# Deel_2_transistor.net
KiCad netlist of a schematic drawn in Altium Designer
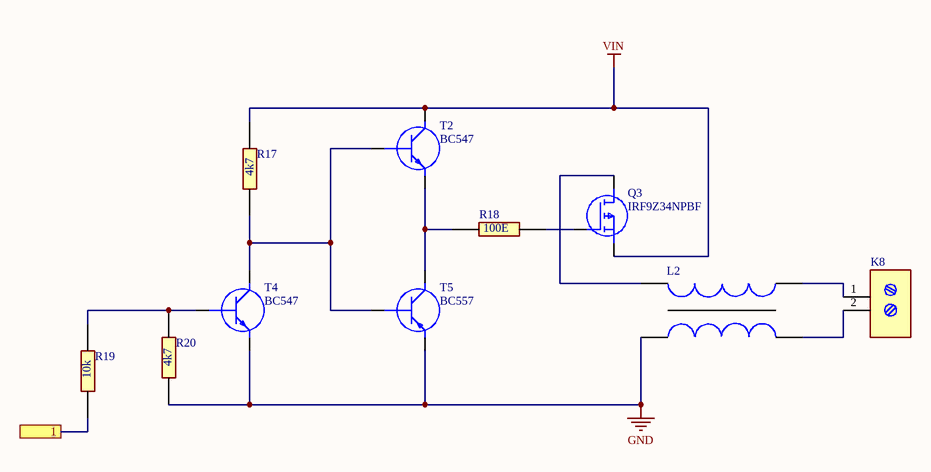
[diagram p0: Deel_2_transistor.SchDoc]

(export (version "E")
  (design (tool "Eeschema 10.0.6"))
  (components
    (comp (ref "K8")
      (value "schroefconnector")
      (footprint "PcbLib1:schroefconnector")
      (description "Connector 1716020000")
      (fields (field (name "MANUFACTURER_PART_NUMBER") "1716020000"))
      (libsource (lib "Schlib_soldeerstation") (part "schroefconnector"))
    )
    (comp (ref "L2")
      (value "cmsmoorspoel")
      (footprint "PcbLib1:CMsmoorspoel")
      (description "Transformer CM2545X171B-10")
      (fields (field (name "MANUFACTURER_PART_NUMBER") "CM2545X171B-10"))
      (libsource (lib "Schlib_soldeerstation") (part "cmsmoorspoel"))
    )
    (comp (ref "Q3")
      (value "IRF9Z34NPBF")
      (footprint "PcbLib1:irf9z34npbf")
      (description "MOSFET (P-Channel)")
      (fields (field (name "MOUSER2 PART NUMBER") "942-IRF9Z34NPBF"))
      (libsource (lib "Schlib_soldeerstation") (part "IRF9Z34NPBF"))
    )
    (comp (ref "R17")
      (value "4k7")
      (footprint "PcbLib1:4k7")
      (description "Resistor")
      (fields
        (field (name "MANUFACTURER_PART_NUMBER") "CPF0805B100RE1")
        (field (name "MOUSER PART NUMBER") "279-CPF0805B100RE1")
      )
      (libsource (lib "Schlib_soldeerstation") (part "4k7"))
    )
    (comp (ref "R18")
      (value "100E")
      (footprint "PcbLib1:100ohm")
      (description "Resistor")
      (fields
        (field (name "MANUFACTURER_PART_NUMBER") "CPF0805B100RE1")
        (field (name "MOUSER PART NUMBER") "279-CPF0805B100RE1")
      )
      (libsource (lib "Schlib_soldeerstation") (part "100ohm"))
    )
    (comp (ref "R19")
      (value "10k")
      (footprint "PcbLib1:10k")
      (description "Resistor")
      (fields
        (field (name "MANUFACTURER_PART_NUMBER") "CPF0805B100RE1")
        (field (name "MOUSER PART NUMBER") "279-CPF0805B100RE1")
      )
      (libsource (lib "Schlib_soldeerstation") (part "10k"))
    )
    (comp (ref "R20")
      (value "4k7")
      (footprint "PcbLib1:4k7")
      (description "Resistor")
      (fields
        (field (name "MANUFACTURER_PART_NUMBER") "CPF0805B100RE1")
        (field (name "MOUSER PART NUMBER") "279-CPF0805B100RE1")
      )
      (libsource (lib "Schlib_soldeerstation") (part "4k7"))
    )
    (comp (ref "T2")
      (value "BC547")
      (footprint "PcbLib1:BC547CBU")
      (description "Transistor BJT NPN")
      (fields (field (name "MANUFACTURER_PART_NUMBER") "BC547CBU"))
      (libsource (lib "Schlib_soldeerstation") (part "BC547CBU"))
    )
    (comp (ref "T4")
      (value "BC547")
      (footprint "PcbLib1:BC547CBU")
      (description "Transistor BJT NPN")
      (fields (field (name "MANUFACTURER_PART_NUMBER") "BC547CBU"))
      (libsource (lib "Schlib_soldeerstation") (part "BC547CBU"))
    )
    (comp (ref "T5")
      (value "BC557")
      (footprint "PcbLib1:BC557C")
      (description "Transistor BJT PNP")
      (fields
        (field (name "MANUFACTURER_PART_NUMBER") "BC557C")
        (field (name "MOUSER PART NUMBER") "771-BC557C")
      )
      (libsource (lib "Schlib_soldeerstation") (part "BC557C"))
    )
  )
  (nets
    (net (code "1") (name "/1") (class "Default")
      (node (ref "R19") (pin "1") (pinfunction "1_1") (pintype "passive"))
    )
    (net (code "2") (name "GND") (class "Default")
      (node (ref "L2") (pin "2") (pinfunction "SEC+_2") (pintype "passive"))
      (node (ref "R20") (pin "1") (pinfunction "1_1") (pintype "passive"))
      (node (ref "T4") (pin "3") (pinfunction "E_3") (pintype "passive"))
      (node (ref "T5") (pin "1") (pinfunction "E_1") (pintype "passive"))
    )
    (net (code "3") (name "Net-(L2-PRI+)") (class "Default")
      (node (ref "L2") (pin "1") (pinfunction "PRI+_1") (pintype "passive"))
      (node (ref "Q3") (pin "3") (pinfunction "D_3") (pintype "passive"))
    )
    (net (code "4") (name "Net-(L2-PRI-)") (class "Default")
      (node (ref "K8") (pin "2") (pinfunction "2_2") (pintype "passive"))
      (node (ref "L2") (pin "4") (pinfunction "PRI-_4") (pintype "passive"))
    )
    (net (code "5") (name "Net-(L2-SEC-)") (class "Default")
      (node (ref "K8") (pin "1") (pinfunction "1_1") (pintype "passive"))
      (node (ref "L2") (pin "3") (pinfunction "SEC-_3") (pintype "passive"))
    )
    (net (code "6") (name "Net-(Q3-G)") (class "Default")
      (node (ref "Q3") (pin "1") (pinfunction "G_1") (pintype "passive"))
      (node (ref "R18") (pin "2") (pinfunction "2_2") (pintype "passive"))
    )
    (net (code "7") (name "Net-(T2-B)") (class "Default")
      (node (ref "R17") (pin "1") (pinfunction "1_1") (pintype "passive"))
      (node (ref "T2") (pin "2") (pinfunction "B_2") (pintype "passive"))
      (node (ref "T4") (pin "1") (pinfunction "C_1") (pintype "passive"))
      (node (ref "T5") (pin "2") (pinfunction "B_2") (pintype "passive"))
    )
    (net (code "8") (name "Net-(T2-E)") (class "Default")
      (node (ref "R18") (pin "1") (pinfunction "1_1") (pintype "passive"))
      (node (ref "T2") (pin "3") (pinfunction "E_3") (pintype "passive"))
      (node (ref "T5") (pin "3") (pinfunction "C_3") (pintype "passive"))
    )
    (net (code "9") (name "Net-(T4-B)") (class "Default")
      (node (ref "R19") (pin "2") (pinfunction "2_2") (pintype "passive"))
      (node (ref "R20") (pin "2") (pinfunction "2_2") (pintype "passive"))
      (node (ref "T4") (pin "2") (pinfunction "B_2") (pintype "passive"))
    )
    (net (code "10") (name "VIN") (class "Default")
      (node (ref "Q3") (pin "2") (pinfunction "S_2") (pintype "passive"))
      (node (ref "R17") (pin "2") (pinfunction "2_2") (pintype "passive"))
      (node (ref "T2") (pin "1") (pinfunction "C_1") (pintype "passive"))
    )
  )
)
